# Front_Node_MiniLock.net
KiCad netlist of a schematic drawn in EAGLE
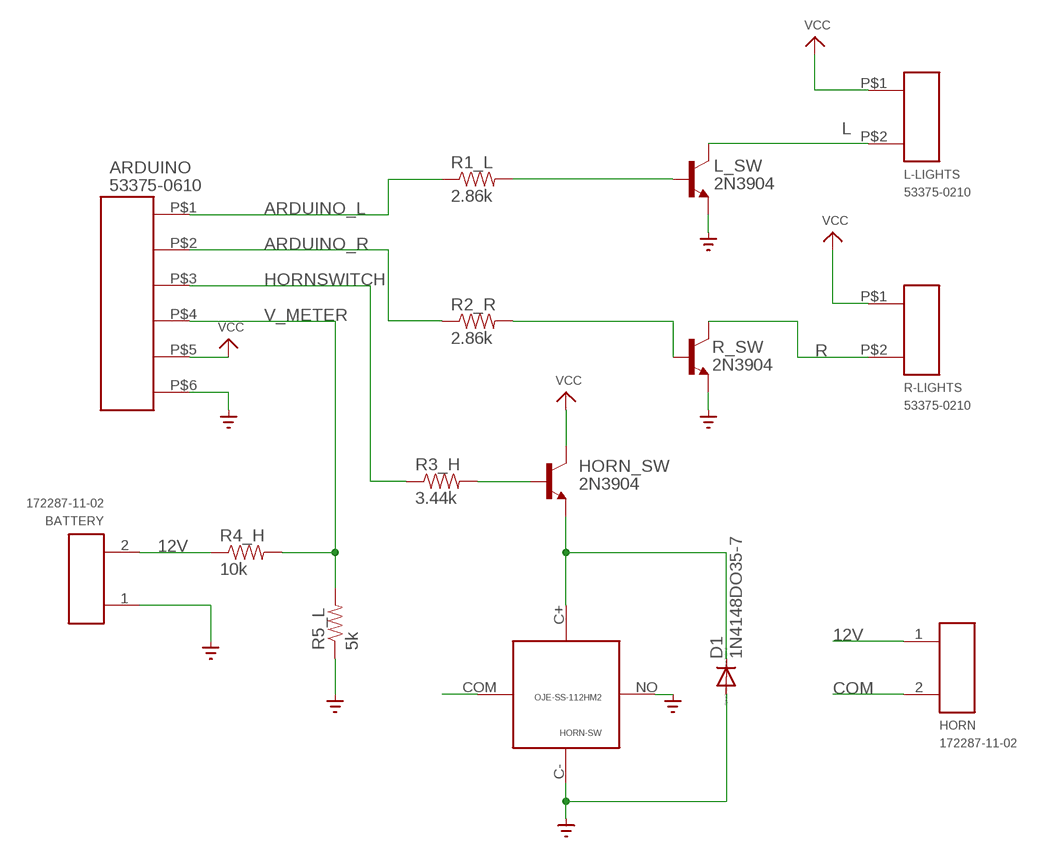
[diagram p0: schematic, sheet 1]

(export (version "E")
  (design (tool "Eeschema 10.0.6"))
  (components
    (comp (ref "ARDUINO")
      (value "53375-0610")
      (footprint "eagle-import:53375-0610-MINI-LOCK")
      (libsource (lib "eagle-import") (part "53375-0610"))
    )
    (comp (ref "BATTERY")
      (value "172287-11-02")
      (footprint "eagle-import:172287-ULTRA-FIT")
      (libsource (lib "eagle-import") (part "172287-11-02"))
    )
    (comp (ref "D1")
      (value "1N4148DO35-7")
      (footprint "eagle-import:DO35-7")
      (libsource (lib "eagle-import") (part "1N4148DO35-7"))
    )
    (comp (ref "HORN")
      (value "172287-11-02")
      (footprint "eagle-import:172287-ULTRA-FIT")
      (libsource (lib "eagle-import") (part "172287-11-02"))
    )
    (comp (ref "HORN-SW")
      (value "OJE-SS-112HM2")
      (footprint "eagle-import:OJE-SS-112HM2-SPST-RELAY")
      (libsource (lib "eagle-import") (part "OJE-SS-112HM2"))
    )
    (comp (ref "HORN_SW")
      (value "2N3904")
      (footprint "eagle-import:TO92")
      (libsource (lib "eagle-import") (part "2N3904"))
    )
    (comp (ref "L-LIGHTS")
      (value "53375-0210")
      (footprint "eagle-import:53375-0210-MINI-LOCK")
      (libsource (lib "eagle-import") (part "53375-0210"))
    )
    (comp (ref "L_SW")
      (value "2N3904")
      (footprint "eagle-import:TO92")
      (libsource (lib "eagle-import") (part "2N3904"))
    )
    (comp (ref "R-LIGHTS")
      (value "53375-0210")
      (footprint "eagle-import:53375-0210-MINI-LOCK")
      (libsource (lib "eagle-import") (part "53375-0210"))
    )
    (comp (ref "R1_L")
      (value "2.86k")
      (footprint "eagle-import:1_6W-RES")
      (libsource (lib "eagle-import") (part "RESISTORPTH-1/6W"))
    )
    (comp (ref "R2_R")
      (value "2.86k")
      (footprint "eagle-import:1_6W-RES")
      (libsource (lib "eagle-import") (part "RESISTORPTH-1/6W"))
    )
    (comp (ref "R3_H")
      (value "3.44k")
      (footprint "eagle-import:1_6W-RES")
      (libsource (lib "eagle-import") (part "RESISTORPTH-1/6W"))
    )
    (comp (ref "R4_H")
      (value "10k")
      (footprint "eagle-import:1_6W-RES")
      (libsource (lib "eagle-import") (part "RESISTORPTH-1/6W"))
    )
    (comp (ref "R5_L")
      (value "5k")
      (footprint "eagle-import:1_6W-RES")
      (libsource (lib "eagle-import") (part "RESISTORPTH-1/6W"))
    )
    (comp (ref "R_SW")
      (value "2N3904")
      (footprint "eagle-import:TO92")
      (libsource (lib "eagle-import") (part "2N3904"))
    )
  )
  (nets
    (net (code "1") (name "/12V") (class "Default")
      (node (ref "BATTERY") (pin "2") (pinfunction "2_2") (pintype "bidirectional"))
      (node (ref "HORN") (pin "1") (pinfunction "1_1") (pintype "bidirectional"))
      (node (ref "R4_H") (pin "1") (pinfunction "1_1") (pintype "passive"))
    )
    (net (code "2") (name "/ARDUINO_L") (class "Default")
      (node (ref "ARDUINO") (pin "P$1") (pinfunction "P$1_P$1") (pintype "bidirectional"))
      (node (ref "R1_L") (pin "1") (pinfunction "1_1") (pintype "passive"))
    )
    (net (code "3") (name "/ARDUINO_R") (class "Default")
      (node (ref "ARDUINO") (pin "P$2") (pinfunction "P$2_P$2") (pintype "bidirectional"))
      (node (ref "R2_R") (pin "1") (pinfunction "1_1") (pintype "passive"))
    )
    (net (code "4") (name "/COM") (class "Default")
      (node (ref "HORN") (pin "2") (pinfunction "2_2") (pintype "bidirectional"))
      (node (ref "HORN-SW") (pin "COM") (pinfunction "COM_COM") (pintype "bidirectional"))
    )
    (net (code "5") (name "/HORNSWITCH") (class "Default")
      (node (ref "ARDUINO") (pin "P$3") (pinfunction "P$3_P$3") (pintype "bidirectional"))
      (node (ref "R3_H") (pin "1") (pinfunction "1_1") (pintype "passive"))
    )
    (net (code "6") (name "/L") (class "Default")
      (node (ref "L-LIGHTS") (pin "P$2") (pinfunction "2_P$2") (pintype "bidirectional"))
      (node (ref "L_SW") (pin "1") (pinfunction "C_1") (pintype "passive"))
    )
    (net (code "7") (name "/R") (class "Default")
      (node (ref "R-LIGHTS") (pin "P$2") (pinfunction "2_P$2") (pintype "bidirectional"))
      (node (ref "R_SW") (pin "1") (pinfunction "C_1") (pintype "passive"))
    )
    (net (code "8") (name "/V_METER") (class "Default")
      (node (ref "ARDUINO") (pin "P$4") (pinfunction "P$4_P$4") (pintype "bidirectional"))
      (node (ref "R4_H") (pin "2") (pinfunction "2_2") (pintype "passive"))
      (node (ref "R5_L") (pin "2") (pinfunction "2_2") (pintype "passive"))
    )
    (net (code "9") (name "GND_") (class "Default")
      (node (ref "ARDUINO") (pin "P$6") (pinfunction "P$6_P$6") (pintype "bidirectional"))
      (node (ref "BATTERY") (pin "1") (pinfunction "1_1") (pintype "bidirectional"))
      (node (ref "D1") (pin "A") (pinfunction "A_A") (pintype "passive"))
      (node (ref "HORN-SW") (pin "C-") (pinfunction "C-_C-") (pintype "bidirectional"))
      (node (ref "HORN-SW") (pin "NO") (pinfunction "NO_NO") (pintype "bidirectional"))
      (node (ref "L_SW") (pin "3") (pinfunction "E_3") (pintype "passive"))
      (node (ref "R5_L") (pin "1") (pinfunction "1_1") (pintype "passive"))
      (node (ref "R_SW") (pin "3") (pinfunction "E_3") (pintype "passive"))
    )
    (net (code "10") (name "Net-(HORN_SW-B)") (class "Default")
      (node (ref "HORN_SW") (pin "2") (pinfunction "B_2") (pintype "passive"))
      (node (ref "R3_H") (pin "2") (pinfunction "2_2") (pintype "passive"))
    )
    (net (code "11") (name "Net-(HORN_SW-E)") (class "Default")
      (node (ref "D1") (pin "C") (pinfunction "C_C") (pintype "passive"))
      (node (ref "HORN-SW") (pin "C+") (pinfunction "C+_C+") (pintype "bidirectional"))
      (node (ref "HORN_SW") (pin "3") (pinfunction "E_3") (pintype "passive"))
    )
    (net (code "12") (name "Net-(L_SW-B)") (class "Default")
      (node (ref "L_SW") (pin "2") (pinfunction "B_2") (pintype "passive"))
      (node (ref "R1_L") (pin "2") (pinfunction "2_2") (pintype "passive"))
    )
    (net (code "13") (name "Net-(R_SW-B)") (class "Default")
      (node (ref "R2_R") (pin "2") (pinfunction "2_2") (pintype "passive"))
      (node (ref "R_SW") (pin "2") (pinfunction "B_2") (pintype "passive"))
    )
    (net (code "14") (name "VCC") (class "Default")
      (node (ref "ARDUINO") (pin "P$5") (pinfunction "P$5_P$5") (pintype "bidirectional"))
      (node (ref "HORN_SW") (pin "1") (pinfunction "C_1") (pintype "passive"))
      (node (ref "L-LIGHTS") (pin "P$1") (pinfunction "1_P$1") (pintype "bidirectional"))
      (node (ref "R-LIGHTS") (pin "P$1") (pinfunction "1_P$1") (pintype "bidirectional"))
    )
  )
)
